# hot.net
KiCad netlist of a schematic drawn in Altium Designer
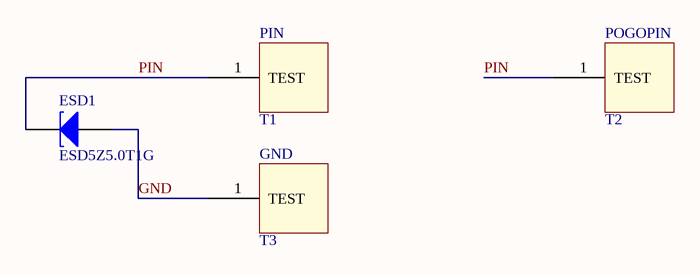
[diagram p0: hot.SchDoc]

(export (version "E")
  (design (tool "Eeschema 10.0.6"))
  (components
    (comp (ref "ESD1")
      (value "ESD5Z5.0T1G")
      (footprint "LC-SOD-523")
      (description "Tunnel Diode - Dependent Source Model")
      (fields (field (name "PUBLISHER") "Altium Limited"))
      (libsource (lib "Miscellaneous Devices") (part "D Tunnel2"))
    )
    (comp (ref "GND") (value "T3") (footprint "PIN") (libsource (lib "MySchLib") (part "TEST_POINT")))
    (comp (ref "PIN") (value "T1") (footprint "PIN") (libsource (lib "MySchLib") (part "TEST_POINT")))
    (comp (ref "POGOPIN") (value "T2") (footprint "POGOPIN") (libsource (lib "MySchLib") (part "TEST_POINT")))
  )
  (nets
    (net (code "1") (name "/GND") (class "Default")
      (node (ref "ESD1") (pin "1") (pinfunction "A_1") (pintype "passive"))
      (node (ref "GND") (pin "1") (pinfunction "TEST_1") (pintype "passive"))
    )
    (net (code "2") (name "/PIN") (class "Default")
      (node (ref "ESD1") (pin "2") (pinfunction "K_2") (pintype "passive"))
      (node (ref "PIN") (pin "1") (pinfunction "TEST_1") (pintype "passive"))
      (node (ref "POGOPIN") (pin "1") (pinfunction "TEST_1") (pintype "passive"))
    )
  )
)
